# Metvoc.net
KiCad netlist of a schematic drawn in EAGLE
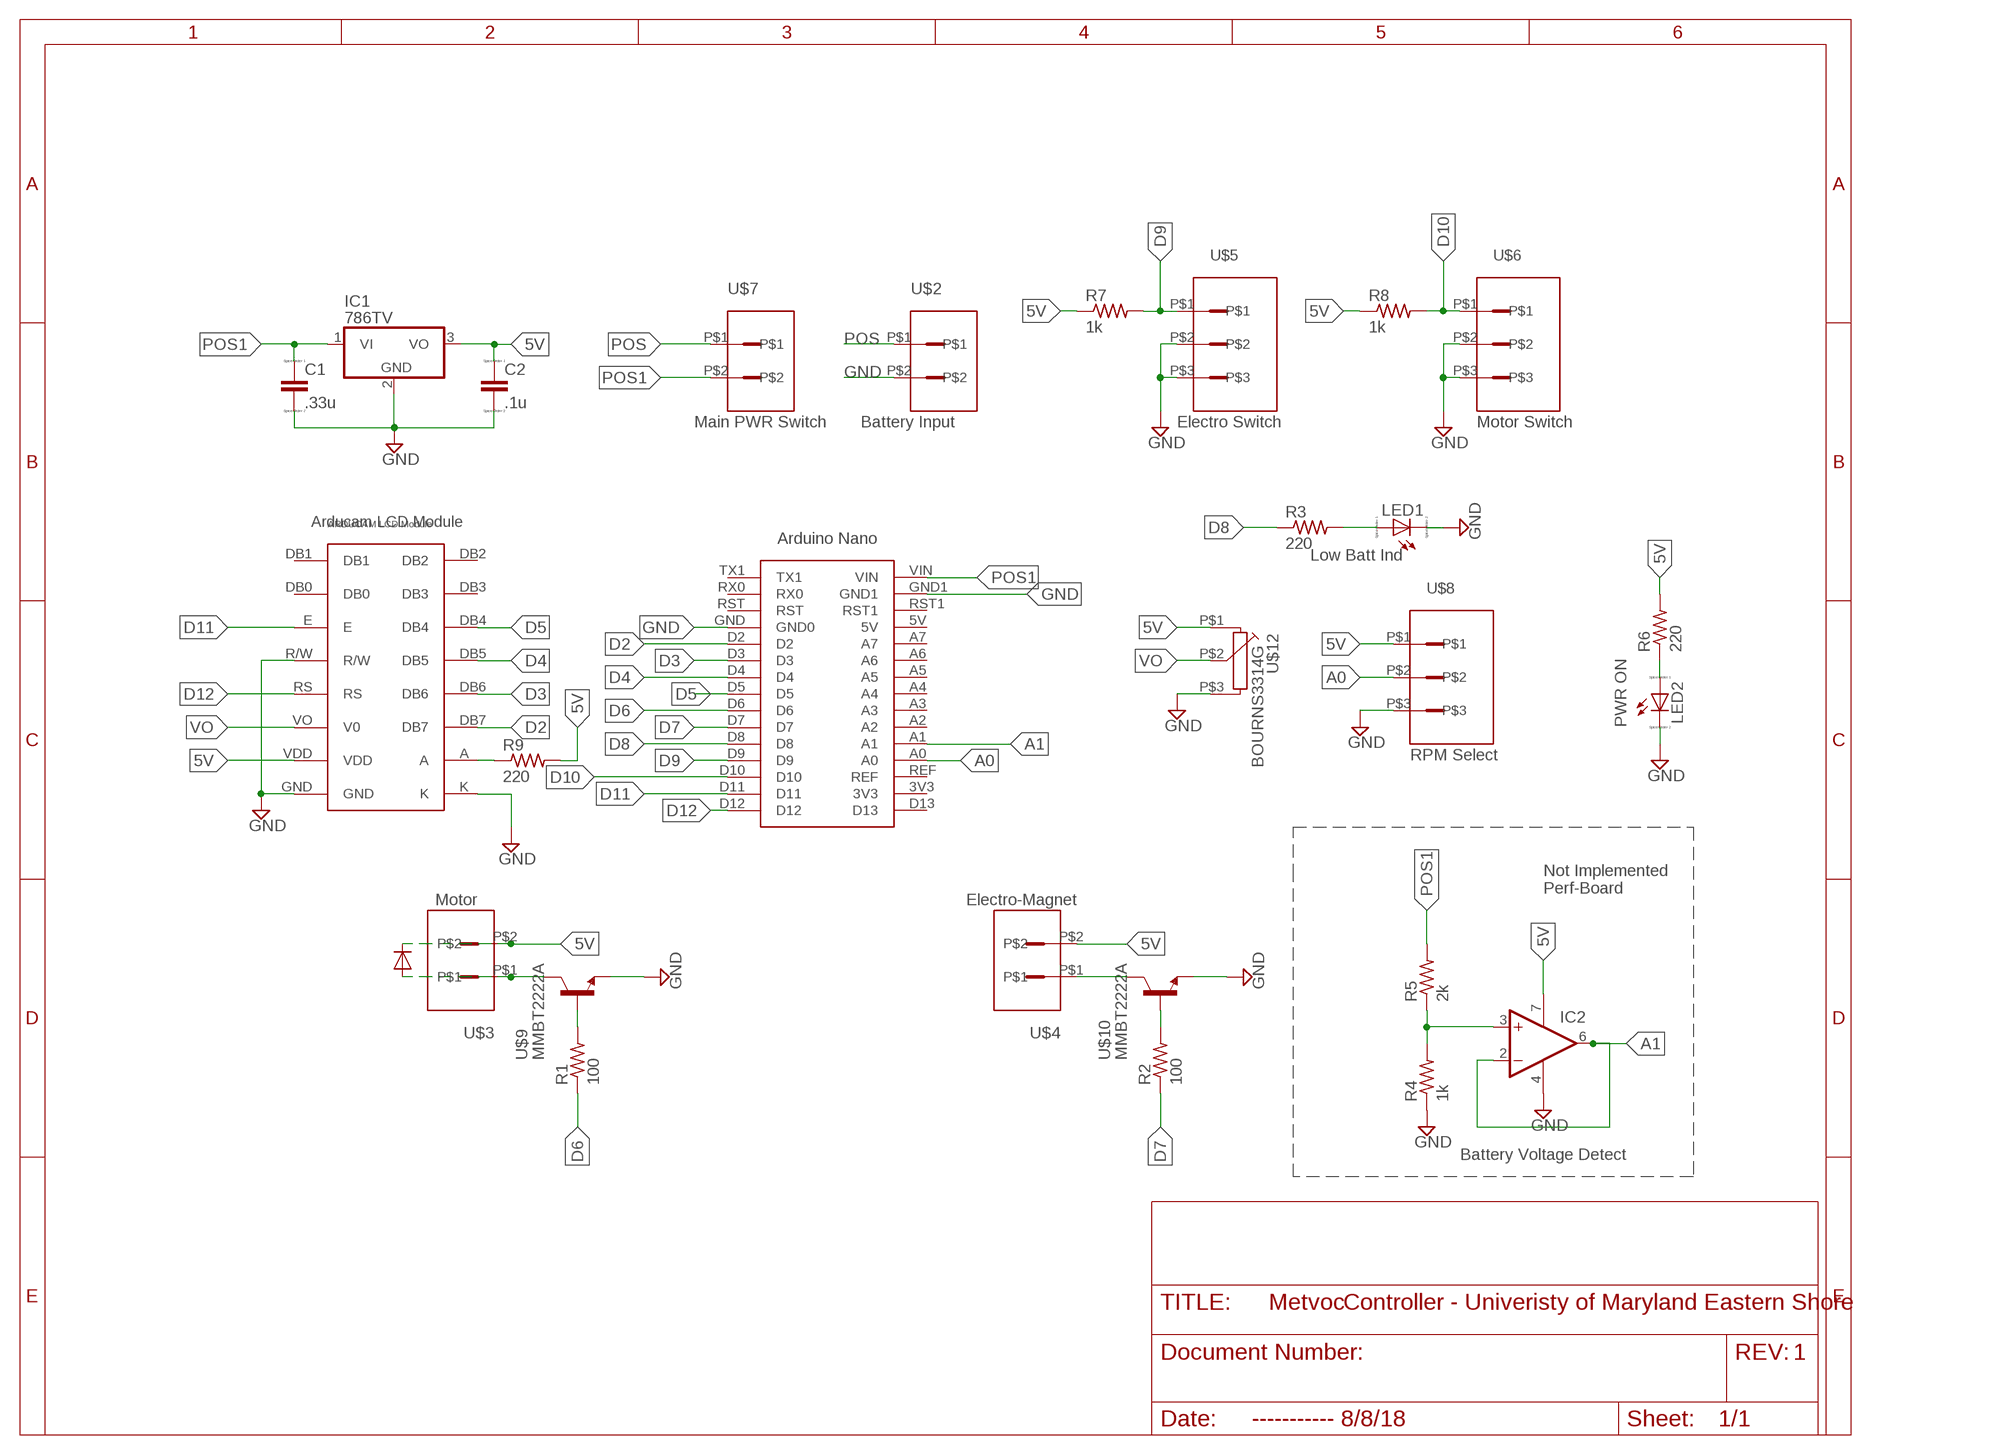
[diagram p0: schematic, sheet 1]

(export (version "E")
  (design (tool "Eeschema 10.0.6"))
  (components
    (comp (ref "C1")
      (value ".33u")
      (footprint "eagle-import:C3216")
      (libsource (lib "eagle-import") (part "CC3216"))
    )
    (comp (ref "C2")
      (value ".1u")
      (footprint "eagle-import:C3216")
      (libsource (lib "eagle-import") (part "CC3216"))
    )
    (comp (ref "IC1")
      (value "786TV")
      (footprint "eagle-import:TO220V")
      (libsource (lib "eagle-import") (part "78TV6"))
    )
    (comp (ref "IC2")
      (value "1AMP_P7+4D")
      (footprint "eagle-import:SO08")
      (libsource (lib "eagle-import") (part "1AMP_P7+4D"))
    )
    (comp (ref "LED1")
      (value "LED_E")
      (footprint "eagle-import:LED_1206")
      (libsource (lib "eagle-import") (part "LED_E"))
    )
    (comp (ref "LED2")
      (value "LED_E")
      (footprint "eagle-import:LED_1206")
      (libsource (lib "eagle-import") (part "LED_E"))
    )
    (comp (ref "R1")
      (value "100")
      (footprint "eagle-import:M1206")
      (libsource (lib "eagle-import") (part "R-US_M1206"))
    )
    (comp (ref "R2")
      (value "100")
      (footprint "eagle-import:M1206")
      (libsource (lib "eagle-import") (part "R-US_M1206"))
    )
    (comp (ref "R3")
      (value "220")
      (footprint "eagle-import:M1206")
      (libsource (lib "eagle-import") (part "R-US_M1206"))
    )
    (comp (ref "R4")
      (value "1k")
      (footprint "eagle-import:M1206")
      (libsource (lib "eagle-import") (part "R-US_M1206"))
    )
    (comp (ref "R5")
      (value "2k")
      (footprint "eagle-import:M1206")
      (libsource (lib "eagle-import") (part "R-US_M1206"))
    )
    (comp (ref "R6")
      (value "220")
      (footprint "eagle-import:M3216")
      (libsource (lib "eagle-import") (part "R-US_M3216"))
    )
    (comp (ref "R7")
      (value "1k")
      (footprint "eagle-import:M1206")
      (libsource (lib "eagle-import") (part "R-US_M1206"))
    )
    (comp (ref "R8")
      (value "1k")
      (footprint "eagle-import:M1206")
      (libsource (lib "eagle-import") (part "R-US_M1206"))
    )
    (comp (ref "R9")
      (value "220")
      (footprint "eagle-import:M1206")
      (libsource (lib "eagle-import") (part "R-US_M1206"))
    )
    (comp (ref "U$1")
      (value "ARDUINO_NANO")
      (footprint "eagle-import:ARDUINONANO")
      (libsource (lib "eagle-import") (part "ARDUINO_NANO"))
    )
    (comp (ref "U$2")
      (value "KF2510-2")
      (footprint "eagle-import:KF2540-2")
      (libsource (lib "eagle-import") (part "KF2510-2"))
    )
    (comp (ref "U$3")
      (value "KF2510-2")
      (footprint "eagle-import:KF2540-2")
      (libsource (lib "eagle-import") (part "KF2510-2"))
    )
    (comp (ref "U$4")
      (value "KF2510-2")
      (footprint "eagle-import:KF2540-2")
      (libsource (lib "eagle-import") (part "KF2510-2"))
    )
    (comp (ref "U$5")
      (value "KF2510-3")
      (footprint "eagle-import:KF2540-3")
      (libsource (lib "eagle-import") (part "KF2510-3"))
    )
    (comp (ref "U$6")
      (value "KF2510-3")
      (footprint "eagle-import:KF2540-3")
      (libsource (lib "eagle-import") (part "KF2510-3"))
    )
    (comp (ref "U$7")
      (value "KF2510-2")
      (footprint "eagle-import:KF2540-2")
      (libsource (lib "eagle-import") (part "KF2510-2"))
    )
    (comp (ref "U$8")
      (value "KF2510-3")
      (footprint "eagle-import:KF2540-3")
      (libsource (lib "eagle-import") (part "KF2510-3"))
    )
    (comp (ref "U$9")
      (value "MMBT2222A")
      (footprint "eagle-import:SOT23")
      (libsource (lib "eagle-import") (part "MMBT2222A"))
    )
    (comp (ref "U$10")
      (value "MMBT2222A")
      (footprint "eagle-import:SOT23")
      (libsource (lib "eagle-import") (part "MMBT2222A"))
    )
    (comp (ref "U$11")
      (value "LCDMODULE")
      (footprint "eagle-import:LCDSCREEN")
      (libsource (lib "eagle-import") (part "LCDMODULE"))
    )
    (comp (ref "U$12")
      (value "BOURNS3314G")
      (footprint "eagle-import:3314POT")
      (libsource (lib "eagle-import") (part "BOURNS3314G"))
    )
  )
  (nets
    (net (code "1") (name "5V") (class "Default")
      (node (ref "C2") (pin "1") (pinfunction "1_1") (pintype "passive"))
      (node (ref "IC1") (pin "3") (pinfunction "VO_3") (pintype "passive"))
      (node (ref "IC2") (pin "7") (pinfunction "V+_7") (pintype "power_in"))
      (node (ref "R6") (pin "2") (pinfunction "2_2") (pintype "passive"))
      (node (ref "R7") (pin "1") (pinfunction "1_1") (pintype "passive"))
      (node (ref "R8") (pin "1") (pinfunction "1_1") (pintype "passive"))
      (node (ref "R9") (pin "2") (pinfunction "2_2") (pintype "passive"))
      (node (ref "U$11") (pin "VDD") (pinfunction "VDD_VDD") (pintype "bidirectional"))
      (node (ref "U$12") (pin "P$1") (pinfunction "1A_P$1") (pintype "passive"))
      (node (ref "U$3") (pin "P$2") (pinfunction "P$2_P$2") (pintype "bidirectional"))
      (node (ref "U$4") (pin "P$2") (pinfunction "P$2_P$2") (pintype "bidirectional"))
      (node (ref "U$8") (pin "P$1") (pinfunction "P$1_P$1") (pintype "bidirectional"))
    )
    (net (code "2") (name "A0") (class "Default")
      (node (ref "U$1") (pin "A0") (pinfunction "A0_A0") (pintype "bidirectional"))
      (node (ref "U$8") (pin "P$2") (pinfunction "P$2_P$2") (pintype "bidirectional"))
    )
    (net (code "3") (name "A1") (class "Default")
      (node (ref "IC2") (pin "2") (pinfunction "-IN_2") (pintype "input"))
      (node (ref "IC2") (pin "6") (pinfunction "OUT_6") (pintype "output"))
      (node (ref "U$1") (pin "A1") (pinfunction "A1_A1") (pintype "bidirectional"))
    )
    (net (code "4") (name "D2") (class "Default")
      (node (ref "U$1") (pin "D2") (pinfunction "D2_D2") (pintype "bidirectional"))
      (node (ref "U$11") (pin "DB7") (pinfunction "DB7_DB7") (pintype "bidirectional"))
    )
    (net (code "5") (name "D3") (class "Default")
      (node (ref "U$1") (pin "D3") (pinfunction "D3_D3") (pintype "bidirectional"))
      (node (ref "U$11") (pin "DB6") (pinfunction "DB6_DB6") (pintype "bidirectional"))
    )
    (net (code "6") (name "D4") (class "Default")
      (node (ref "U$1") (pin "D4") (pinfunction "D4_D4") (pintype "bidirectional"))
      (node (ref "U$11") (pin "DB5") (pinfunction "DB5_DB5") (pintype "bidirectional"))
    )
    (net (code "7") (name "D5") (class "Default")
      (node (ref "U$1") (pin "D5") (pinfunction "D5_D5") (pintype "bidirectional"))
      (node (ref "U$11") (pin "DB4") (pinfunction "DB4_DB4") (pintype "bidirectional"))
    )
    (net (code "8") (name "D6") (class "Default")
      (node (ref "R1") (pin "1") (pinfunction "1_1") (pintype "passive"))
      (node (ref "U$1") (pin "D6") (pinfunction "D6_D6") (pintype "bidirectional"))
    )
    (net (code "9") (name "D7") (class "Default")
      (node (ref "R2") (pin "1") (pinfunction "1_1") (pintype "passive"))
      (node (ref "U$1") (pin "D7") (pinfunction "D7_D7") (pintype "bidirectional"))
    )
    (net (code "10") (name "D8") (class "Default")
      (node (ref "R3") (pin "1") (pinfunction "1_1") (pintype "passive"))
      (node (ref "U$1") (pin "D8") (pinfunction "D8_D8") (pintype "bidirectional"))
    )
    (net (code "11") (name "D9") (class "Default")
      (node (ref "R7") (pin "2") (pinfunction "2_2") (pintype "passive"))
      (node (ref "U$1") (pin "D9") (pinfunction "D9_D9") (pintype "bidirectional"))
      (node (ref "U$5") (pin "P$1") (pinfunction "P$1_P$1") (pintype "bidirectional"))
    )
    (net (code "12") (name "D10") (class "Default")
      (node (ref "R8") (pin "2") (pinfunction "2_2") (pintype "passive"))
      (node (ref "U$1") (pin "D10") (pinfunction "D10_D10") (pintype "bidirectional"))
      (node (ref "U$6") (pin "P$1") (pinfunction "P$1_P$1") (pintype "bidirectional"))
    )
    (net (code "13") (name "D11") (class "Default")
      (node (ref "U$1") (pin "D11") (pinfunction "D11_D11") (pintype "bidirectional"))
      (node (ref "U$11") (pin "E") (pinfunction "E_E") (pintype "bidirectional"))
    )
    (net (code "14") (name "D12") (class "Default")
      (node (ref "U$1") (pin "D12") (pinfunction "D12_D12") (pintype "bidirectional"))
      (node (ref "U$11") (pin "RS") (pinfunction "RS_RS") (pintype "bidirectional"))
    )
    (net (code "15") (name "GND") (class "Default")
      (node (ref "C1") (pin "2") (pinfunction "2_2") (pintype "passive"))
      (node (ref "C2") (pin "2") (pinfunction "2_2") (pintype "passive"))
      (node (ref "IC1") (pin "2") (pinfunction "GND_2") (pintype "passive"))
      (node (ref "IC2") (pin "4") (pinfunction "V-_4") (pintype "power_in"))
      (node (ref "LED1") (pin "C") (pinfunction "C_C") (pintype "passive"))
      (node (ref "LED2") (pin "C") (pinfunction "C_C") (pintype "passive"))
      (node (ref "R4") (pin "1") (pinfunction "1_1") (pintype "passive"))
      (node (ref "U$1") (pin "GND") (pinfunction "GND0_GND") (pintype "bidirectional"))
      (node (ref "U$1") (pin "GND1") (pinfunction "GND1_GND1") (pintype "bidirectional"))
      (node (ref "U$10") (pin "2") (pinfunction "E_2") (pintype "passive"))
      (node (ref "U$11") (pin "GND") (pinfunction "GND_GND") (pintype "bidirectional"))
      (node (ref "U$11") (pin "K") (pinfunction "K_K") (pintype "bidirectional"))
      (node (ref "U$11") (pin "R/W") (pinfunction "R/W_R/W") (pintype "bidirectional"))
      (node (ref "U$12") (pin "P$3") (pinfunction "1E_P$3") (pintype "passive"))
      (node (ref "U$2") (pin "P$2") (pinfunction "P$2_P$2") (pintype "bidirectional"))
      (node (ref "U$5") (pin "P$2") (pinfunction "P$2_P$2") (pintype "bidirectional"))
      (node (ref "U$5") (pin "P$3") (pinfunction "P$3_P$3") (pintype "bidirectional"))
      (node (ref "U$6") (pin "P$2") (pinfunction "P$2_P$2") (pintype "bidirectional"))
      (node (ref "U$6") (pin "P$3") (pinfunction "P$3_P$3") (pintype "bidirectional"))
      (node (ref "U$8") (pin "P$3") (pinfunction "P$3_P$3") (pintype "bidirectional"))
      (node (ref "U$9") (pin "2") (pinfunction "E_2") (pintype "passive"))
    )
    (net (code "16") (name "Net-(IC2-+IN)") (class "Default")
      (node (ref "IC2") (pin "3") (pinfunction "+IN_3") (pintype "input"))
      (node (ref "R4") (pin "2") (pinfunction "2_2") (pintype "passive"))
      (node (ref "R5") (pin "1") (pinfunction "1_1") (pintype "passive"))
    )
    (net (code "17") (name "Net-(LED1-PadA)") (class "Default")
      (node (ref "LED1") (pin "A") (pinfunction "A_A") (pintype "passive"))
      (node (ref "R3") (pin "2") (pinfunction "2_2") (pintype "passive"))
    )
    (net (code "18") (name "Net-(LED2-PadA)") (class "Default")
      (node (ref "LED2") (pin "A") (pinfunction "A_A") (pintype "passive"))
      (node (ref "R6") (pin "1") (pinfunction "1_1") (pintype "passive"))
    )
    (net (code "19") (name "Net-(R9-Pad1)") (class "Default")
      (node (ref "R9") (pin "1") (pinfunction "1_1") (pintype "passive"))
      (node (ref "U$11") (pin "A") (pinfunction "A_A") (pintype "bidirectional"))
    )
    (net (code "20") (name "Net-(U$9-B)") (class "Default")
      (node (ref "R1") (pin "2") (pinfunction "2_2") (pintype "passive"))
      (node (ref "U$9") (pin "1") (pinfunction "B_1") (pintype "passive"))
    )
    (net (code "21") (name "Net-(U$9-C)") (class "Default")
      (node (ref "U$3") (pin "P$1") (pinfunction "P$1_P$1") (pintype "bidirectional"))
      (node (ref "U$9") (pin "3") (pinfunction "C_3") (pintype "passive"))
    )
    (net (code "22") (name "Net-(U$10-B)") (class "Default")
      (node (ref "R2") (pin "2") (pinfunction "2_2") (pintype "passive"))
      (node (ref "U$10") (pin "1") (pinfunction "B_1") (pintype "passive"))
    )
    (net (code "23") (name "Net-(U$10-C)") (class "Default")
      (node (ref "U$10") (pin "3") (pinfunction "C_3") (pintype "passive"))
      (node (ref "U$4") (pin "P$1") (pinfunction "P$1_P$1") (pintype "bidirectional"))
    )
    (net (code "24") (name "POS") (class "Default")
      (node (ref "U$2") (pin "P$1") (pinfunction "P$1_P$1") (pintype "bidirectional"))
      (node (ref "U$7") (pin "P$1") (pinfunction "P$1_P$1") (pintype "bidirectional"))
    )
    (net (code "25") (name "POS1") (class "Default")
      (node (ref "C1") (pin "1") (pinfunction "1_1") (pintype "passive"))
      (node (ref "IC1") (pin "1") (pinfunction "VI_1") (pintype "input"))
      (node (ref "R5") (pin "2") (pinfunction "2_2") (pintype "passive"))
      (node (ref "U$1") (pin "VIN") (pinfunction "VIN_VIN") (pintype "bidirectional"))
      (node (ref "U$7") (pin "P$2") (pinfunction "P$2_P$2") (pintype "bidirectional"))
    )
    (net (code "26") (name "VO") (class "Default")
      (node (ref "U$11") (pin "VO") (pinfunction "V0_VO") (pintype "bidirectional"))
      (node (ref "U$12") (pin "P$2") (pinfunction "1S_P$2") (pintype "passive"))
    )
    (net (code "27") (name "unconnected-(U$1-Pad3V3)") (class "Default")
      (node (ref "U$1") (pin "3V3") (pinfunction "3V3_3V3") (pintype "bidirectional"))
    )
    (net (code "28") (name "unconnected-(U$1-Pad5V)") (class "Default")
      (node (ref "U$1") (pin "5V") (pinfunction "5V_5V") (pintype "bidirectional"))
    )
    (net (code "29") (name "unconnected-(U$1-PadA2)") (class "Default")
      (node (ref "U$1") (pin "A2") (pinfunction "A2_A2") (pintype "bidirectional"))
    )
    (net (code "30") (name "unconnected-(U$1-PadA3)") (class "Default")
      (node (ref "U$1") (pin "A3") (pinfunction "A3_A3") (pintype "bidirectional"))
    )
    (net (code "31") (name "unconnected-(U$1-PadA4)") (class "Default")
      (node (ref "U$1") (pin "A4") (pinfunction "A4_A4") (pintype "bidirectional"))
    )
    (net (code "32") (name "unconnected-(U$1-PadA5)") (class "Default")
      (node (ref "U$1") (pin "A5") (pinfunction "A5_A5") (pintype "bidirectional"))
    )
    (net (code "33") (name "unconnected-(U$1-PadA6)") (class "Default")
      (node (ref "U$1") (pin "A6") (pinfunction "A6_A6") (pintype "bidirectional"))
    )
    (net (code "34") (name "unconnected-(U$1-PadA7)") (class "Default")
      (node (ref "U$1") (pin "A7") (pinfunction "A7_A7") (pintype "bidirectional"))
    )
    (net (code "35") (name "unconnected-(U$1-PadD13)") (class "Default")
      (node (ref "U$1") (pin "D13") (pinfunction "D13_D13") (pintype "bidirectional"))
    )
    (net (code "36") (name "unconnected-(U$1-PadREF)") (class "Default")
      (node (ref "U$1") (pin "REF") (pinfunction "REF_REF") (pintype "bidirectional"))
    )
    (net (code "37") (name "unconnected-(U$1-PadRST)") (class "Default")
      (node (ref "U$1") (pin "RST") (pinfunction "RST_RST") (pintype "bidirectional"))
    )
    (net (code "38") (name "unconnected-(U$1-PadRST1)") (class "Default")
      (node (ref "U$1") (pin "RST1") (pinfunction "RST1_RST1") (pintype "bidirectional"))
    )
    (net (code "39") (name "unconnected-(U$1-PadRX0)") (class "Default")
      (node (ref "U$1") (pin "RX0") (pinfunction "RX0_RX0") (pintype "bidirectional"))
    )
    (net (code "40") (name "unconnected-(U$1-PadTX1)") (class "Default")
      (node (ref "U$1") (pin "TX1") (pinfunction "TX1_TX1") (pintype "bidirectional"))
    )
    (net (code "41") (name "unconnected-(U$11-PadDB0)") (class "Default")
      (node (ref "U$11") (pin "DB0") (pinfunction "DB0_DB0") (pintype "bidirectional"))
    )
    (net (code "42") (name "unconnected-(U$11-PadDB1)") (class "Default")
      (node (ref "U$11") (pin "DB1") (pinfunction "DB1_DB1") (pintype "bidirectional"))
    )
    (net (code "43") (name "unconnected-(U$11-PadDB2)") (class "Default")
      (node (ref "U$11") (pin "DB2") (pinfunction "DB2_DB2") (pintype "bidirectional"))
    )
    (net (code "44") (name "unconnected-(U$11-PadDB3)") (class "Default")
      (node (ref "U$11") (pin "DB3") (pinfunction "DB3_DB3") (pintype "bidirectional"))
    )
  )
)
